# power.net
KiCad netlist of a schematic drawn in Altium Designer
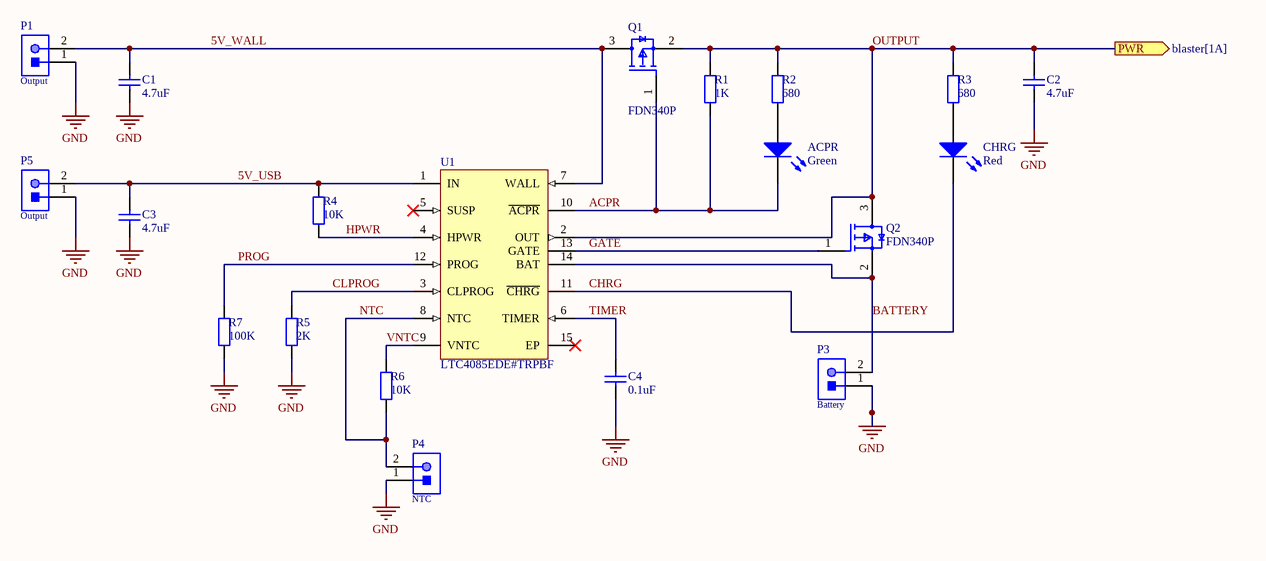
[diagram p0: power.SchDoc]

(export (version "E")
  (design (tool "Eeschema 10.0.6"))
  (components
    (comp (ref "ACPR")
      (value "Green")
      (footprint "0805_A")
      (description "SMD mono-color Chip LED, WL-SMCW, Green")
      (fields (field (name "PARTNUMBER") "150080GS75000") (field (name "MANUFACTURER") "Wuerth Elektronik"))
      (libsource (lib "Altium Content Vault") (part "WE-LED_K1A2-2"))
    )
    (comp (ref "C1")
      (value "4.7uF")
      (footprint "CAPC2013X145X50ML20T25")
      (fields (field (name "MANUFACTURER") "Kemet") (field (name "PART NUMBER") "C0805C475K3PACTU"))
      (libsource (lib "Altium Content Vault") (part "CAP"))
    )
    (comp (ref "C2")
      (value "4.7uF")
      (footprint "CAPC2013X145X50ML20T25")
      (fields (field (name "MANUFACTURER") "Kemet") (field (name "PART NUMBER") "C0805C475K3PACTU"))
      (libsource (lib "Altium Content Vault") (part "CAP"))
    )
    (comp (ref "C3")
      (value "4.7uF")
      (footprint "CAPC2013X145X50ML20T25")
      (fields (field (name "MANUFACTURER") "Kemet") (field (name "PART NUMBER") "C0805C475K3PACTU"))
      (libsource (lib "Altium Content Vault") (part "CAP"))
    )
    (comp (ref "C4")
      (value "0.1uF")
      (footprint "CAPC2013X135X45ML10T25")
      (description "Chip Capacitor, 0.1 uF, +/- 10%, 50 V, -55 to 125 degC, 0805 (2012 Metric), RoHS, Tape and Reel")
      (fields (field (name "VOLTAGE") "50V") (field (name "TOLERANCE") "10%"))
      (libsource (lib "Altium Content Vault") (part "CAP-NP-2"))
    )
    (comp (ref "CHRG")
      (value "Red")
      (footprint "0805_A")
      (description "SMD mono-color Chip LED, WL-SMCW, Red")
      (fields (field (name "PARTNUMBER") "150080RS75000") (field (name "MANUFACTURER") "Wuerth Elektronik"))
      (libsource (lib "Altium Content Vault") (part "WE-LED_K1A2-2"))
    )
    (comp (ref "P1")
      (value "Output")
      (footprint "61300211121")
      (description "THT Vertical Pin Header WR-PHD, Pitch 2.54 mm, Single Row, 2 pins")
      (fields
        (field (name "MANUFACTURER") "Wurth Elektronik")
        (field (name "PART NUMBER") "61300211121")
        (field (name "PUBLISHER") "WurthElektronik")
      )
      (libsource (lib "Altium Content Vault") (part "WE-CN-1P-M-R2"))
    )
    (comp (ref "P3")
      (value "Battery")
      (footprint "61300211121")
      (description "THT Vertical Pin Header WR-PHD, Pitch 2.54 mm, Single Row, 2 pins")
      (fields
        (field (name "MANUFACTURER") "Wurth Elektronik")
        (field (name "PART NUMBER") "61300211121")
        (field (name "PUBLISHER") "WurthElektronik")
      )
      (libsource (lib "Altium Content Vault") (part "WE-CN-1P-M-R2"))
    )
    (comp (ref "P4")
      (value "NTC")
      (footprint "61300211121")
      (description "THT Vertical Pin Header WR-PHD, Pitch 2.54 mm, Single Row, 2 pins")
      (fields
        (field (name "MANUFACTURER") "Wurth Elektronik")
        (field (name "PART NUMBER") "61300211121")
        (field (name "PUBLISHER") "WurthElektronik")
      )
      (libsource (lib "") (part "WE-CN-1P-M-R2_1"))
    )
    (comp (ref "P5")
      (value "Output")
      (footprint "61300211121")
      (description "THT Vertical Pin Header WR-PHD, Pitch 2.54 mm, Single Row, 2 pins")
      (fields
        (field (name "MANUFACTURER") "Wurth Elektronik")
        (field (name "PART NUMBER") "61300211121")
        (field (name "PUBLISHER") "WurthElektronik")
      )
      (libsource (lib "Altium Content Vault") (part "WE-CN-1P-M-R2"))
    )
    (comp (ref "Q1")
      (value "FDN340P")
      (footprint "FP-527AG-MFG")
      (description "MOSFET P-CH 20V 2A SSOT3")
      (libsource (lib "Altium Content Vault") (part "d23f43cc42f60b967b7caccf14518fd"))
    )
    (comp (ref "Q2")
      (value "FDN340P")
      (footprint "FP-527AG-MFG")
      (description "MOSFET P-CH 20V 2A SSOT3")
      (libsource (lib "Altium Content Vault") (part "d23f43cc42f60b967b7caccf14518fd"))
    )
    (comp (ref "R1")
      (value "1K")
      (footprint "RESC2013X50X30ML20T20")
      (fields (field (name "PART NUMBER") "CRCW08051K00FKEA") (field (name "MANUFACTURER") "Vishay Dale"))
      (libsource (lib "Altium Content Vault") (part "RES"))
    )
    (comp (ref "R2")
      (value "680")
      (footprint "RESC2013X50X30ML20T20")
      (fields (field (name "MANUFACTURER") "Vishay Dale") (field (name "PART NUMBER") "CRCW0805680RFKEA"))
      (libsource (lib "Altium Content Vault") (part "RES"))
    )
    (comp (ref "R3")
      (value "680")
      (footprint "RESC2013X50X30ML20T20")
      (fields (field (name "MANUFACTURER") "Vishay Dale") (field (name "PART NUMBER") "CRCW0805680RFKEA"))
      (libsource (lib "Altium Content Vault") (part "RES"))
    )
    (comp (ref "R4")
      (value "10K")
      (footprint "RESC2013X70X40ML20T20")
      (fields (field (name "PART NUMBER") "ERJ-6GEYJ103V") (field (name "MANUFACTURER") "Panasonic"))
      (libsource (lib "Altium Content Vault") (part "RES"))
    )
    (comp (ref "R5")
      (value "2K")
      (footprint "RESC2013X60X35ML10T20")
      (fields (field (name "MANUFACTURER") "Yageo") (field (name "PART NUMBER") "RC0805JR-072KL"))
      (libsource (lib "Altium Content Vault") (part "RES"))
    )
    (comp (ref "R6")
      (value "10K")
      (footprint "RESC2012X145X30ML20T15")
      (fields (field (name "MANUFACTURER") "Vishay Dale") (field (name "PART NUMBER") "NTHS0805N02N1002JE"))
      (libsource (lib "Altium Content Vault") (part "RES"))
    )
    (comp (ref "R7")
      (value "100K")
      (footprint "RESC2013X70X40ML20T20")
      (fields (field (name "PART NUMBER") "ERJ-6GEYJ104V") (field (name "MANUFACTURER") "Panasonic"))
      (libsource (lib "Altium Content Vault") (part "RES"))
    )
    (comp (ref "U1")
      (value "LTC4085EDE#TRPBF")
      (footprint "LT-DE-14_V")
      (fields (field (name "MANUFACTURER") "Linear Technology"))
      (libsource (lib "Altium Content Vault") (part "LT-LTC4085-DE-14"))
    )
  )
  (nets
    (net (code "1") (name "/5V_USB") (class "Default")
      (node (ref "C3") (pin "2") (pinfunction "2_2") (pintype "passive"))
      (node (ref "P5") (pin "2") (pinfunction "2_2") (pintype "passive"))
      (node (ref "R4") (pin "2") (pinfunction "2_2") (pintype "passive"))
      (node (ref "U1") (pin "1") (pinfunction "IN_1") (pintype "power_in"))
    )
    (net (code "2") (name "/5V_WALL") (class "Default")
      (node (ref "C1") (pin "2") (pinfunction "2_2") (pintype "passive"))
      (node (ref "P1") (pin "2") (pinfunction "2_2") (pintype "passive"))
      (node (ref "Q1") (pin "3") (pinfunction "D_3") (pintype "passive"))
      (node (ref "U1") (pin "7") (pinfunction "WALL_7") (pintype "input"))
    )
    (net (code "3") (name "/ACPR") (class "Default")
      (node (ref "ACPR") (pin "1") (pinfunction "K_1") (pintype "passive"))
      (node (ref "Q1") (pin "1") (pinfunction "G_1") (pintype "passive"))
      (node (ref "R1") (pin "1") (pinfunction "1_1") (pintype "passive"))
      (node (ref "U1") (pin "10") (pinfunction "~{ACPR}_10") (pintype "tri_state"))
    )
    (net (code "4") (name "/BATTERY") (class "Default")
      (node (ref "P3") (pin "2") (pinfunction "2_2") (pintype "passive"))
      (node (ref "Q2") (pin "2") (pinfunction "S_2") (pintype "passive"))
      (node (ref "U1") (pin "14") (pinfunction "BAT_14") (pintype "power_in"))
    )
    (net (code "5") (name "/CHRG") (class "Default")
      (node (ref "CHRG") (pin "1") (pinfunction "K_1") (pintype "passive"))
      (node (ref "U1") (pin "11") (pinfunction "~{CHRG}_11") (pintype "tri_state"))
    )
    (net (code "6") (name "/CLPROG") (class "Default")
      (node (ref "R5") (pin "2") (pinfunction "2_2") (pintype "passive"))
      (node (ref "U1") (pin "3") (pinfunction "CLPROG_3") (pintype "input"))
    )
    (net (code "7") (name "/GATE") (class "Default")
      (node (ref "Q2") (pin "1") (pinfunction "G_1") (pintype "passive"))
      (node (ref "U1") (pin "13") (pinfunction "GATE_13") (pintype "tri_state"))
    )
    (net (code "8") (name "/HPWR") (class "Default")
      (node (ref "R4") (pin "1") (pinfunction "1_1") (pintype "passive"))
      (node (ref "U1") (pin "4") (pinfunction "HPWR_4") (pintype "input"))
    )
    (net (code "9") (name "/NTC") (class "Default")
      (node (ref "P4") (pin "2") (pinfunction "2_2") (pintype "passive"))
      (node (ref "R6") (pin "1") (pinfunction "1_1") (pintype "passive"))
      (node (ref "U1") (pin "8") (pinfunction "NTC_8") (pintype "input"))
    )
    (net (code "10") (name "/OUTPUT") (class "Default")
      (node (ref "C2") (pin "2") (pinfunction "2_2") (pintype "passive"))
      (node (ref "Q1") (pin "2") (pinfunction "S_2") (pintype "passive"))
      (node (ref "Q2") (pin "3") (pinfunction "D_3") (pintype "passive"))
      (node (ref "R1") (pin "2") (pinfunction "2_2") (pintype "passive"))
      (node (ref "R2") (pin "2") (pinfunction "2_2") (pintype "passive"))
      (node (ref "R3") (pin "2") (pinfunction "2_2") (pintype "passive"))
      (node (ref "U1") (pin "2") (pinfunction "OUT_2") (pintype "output"))
    )
    (net (code "11") (name "/PROG") (class "Default")
      (node (ref "R7") (pin "2") (pinfunction "2_2") (pintype "passive"))
      (node (ref "U1") (pin "12") (pinfunction "PROG_12") (pintype "input"))
    )
    (net (code "12") (name "/TIMER") (class "Default")
      (node (ref "C4") (pin "2") (pinfunction "2_2") (pintype "passive"))
      (node (ref "U1") (pin "6") (pinfunction "TIMER_6") (pintype "input"))
    )
    (net (code "13") (name "/VNTC") (class "Default")
      (node (ref "R6") (pin "2") (pinfunction "2_2") (pintype "passive"))
      (node (ref "U1") (pin "9") (pinfunction "VNTC_9") (pintype "passive"))
    )
    (net (code "14") (name "GND") (class "Default")
      (node (ref "C1") (pin "1") (pinfunction "1_1") (pintype "passive"))
      (node (ref "C2") (pin "1") (pinfunction "1_1") (pintype "passive"))
      (node (ref "C3") (pin "1") (pinfunction "1_1") (pintype "passive"))
      (node (ref "C4") (pin "1") (pinfunction "1_1") (pintype "passive"))
      (node (ref "P1") (pin "1") (pinfunction "1_1") (pintype "passive"))
      (node (ref "P3") (pin "1") (pinfunction "1_1") (pintype "passive"))
      (node (ref "P4") (pin "1") (pinfunction "1_1") (pintype "passive"))
      (node (ref "P5") (pin "1") (pinfunction "1_1") (pintype "passive"))
      (node (ref "R5") (pin "1") (pinfunction "1_1") (pintype "passive"))
      (node (ref "R7") (pin "1") (pinfunction "1_1") (pintype "passive"))
    )
    (net (code "15") (name "Net-(ACPR-A)") (class "Default")
      (node (ref "ACPR") (pin "2") (pinfunction "A_2") (pintype "passive"))
      (node (ref "R2") (pin "1") (pinfunction "1_1") (pintype "passive"))
    )
    (net (code "16") (name "Net-(CHRG-A)") (class "Default")
      (node (ref "CHRG") (pin "2") (pinfunction "A_2") (pintype "passive"))
      (node (ref "R3") (pin "1") (pinfunction "1_1") (pintype "passive"))
    )
    (net (code "17") (name "unconnected-(U1-EP-Pad15)") (class "Default")
      (node (ref "U1") (pin "15") (pinfunction "EP_15") (pintype "power_in+no_connect"))
    )
    (net (code "18") (name "unconnected-(U1-SUSP-Pad5)") (class "Default")
      (node (ref "U1") (pin "5") (pinfunction "SUSP_5") (pintype "input+no_connect"))
    )
  )
)
